# ADC.net
KiCad netlist of a schematic drawn in Altium Designer
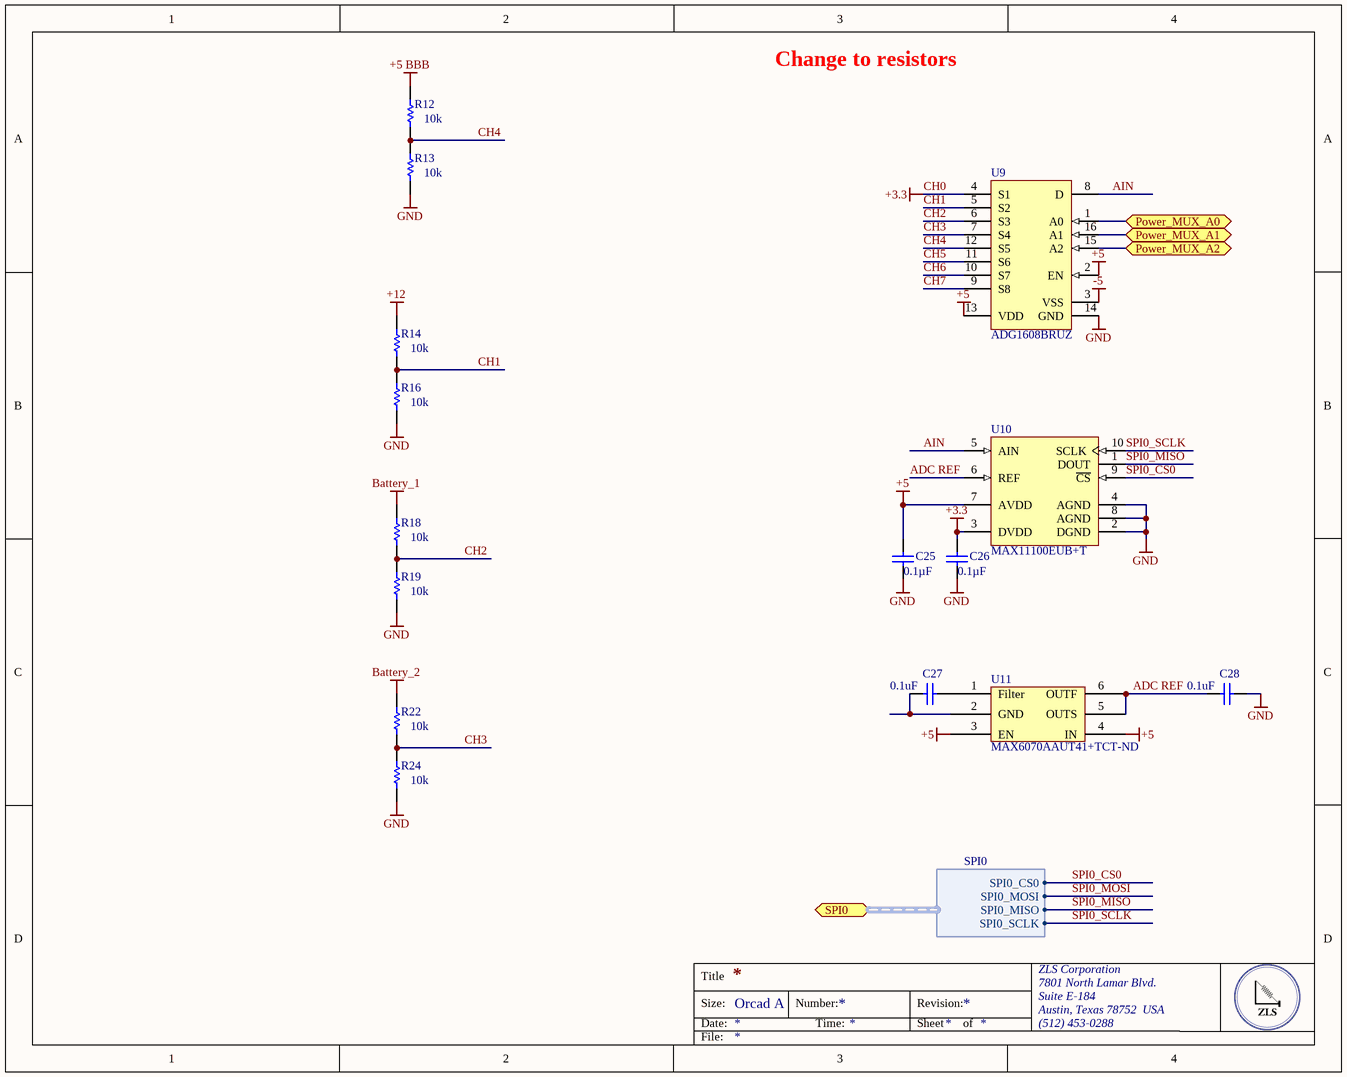
[diagram p0: ADC.SchDoc]

(export (version "E")
  (design (tool "Eeschema 10.0.6"))
  (components
    (comp (ref "C25")
      (value "CAP CER 0.1UF 25V X7R 0805")
      (footprint "CAPC0805(2012)145_N")
      (fields
        (field (name "MANUFACTURER") "Murata Electronics North America")
        (field (name "MANUFACTURER PART NUMBER") "GRM21BR71E104KA01L")
        (field (name "CAPACITANCE") "0.1µF")
        (field (name "TOLERANCE") "±10%")
      )
      (libsource (lib "Altium Content Vault") (part "CMP-1036-04795-1"))
    )
    (comp (ref "C26")
      (value "CAP CER 0.1UF 25V X7R 0805")
      (footprint "CAPC0805(2012)145_N")
      (fields
        (field (name "MANUFACTURER") "Murata Electronics North America")
        (field (name "MANUFACTURER PART NUMBER") "GRM21BR71E104KA01L")
        (field (name "CAPACITANCE") "0.1µF")
        (field (name "TOLERANCE") "±10%")
      )
      (libsource (lib "Altium Content Vault") (part "CMP-1036-04795-1"))
    )
    (comp (ref "C27")
      (value "0.1uF")
      (footprint "CAPC0402(1005)60_L")
      (description "CAP CER 0.1UF 10V X7R 0402")
      (fields
        (field (name "MANUFACTURER") "Murata Electronics North America")
        (field (name "MANUFACTURER PART NUMBER") "GRM155R71A104KA01D")
      )
      (libsource (lib "Altium Content Vault") (part "CMP-1034-00252-1"))
    )
    (comp (ref "C28")
      (value "0.1uF")
      (footprint "CAPC0402(1005)60_L")
      (description "CAP CER 0.1UF 10V X7R 0402")
      (fields
        (field (name "MANUFACTURER") "Murata Electronics North America")
        (field (name "MANUFACTURER PART NUMBER") "GRM155R71A104KA01D")
      )
      (libsource (lib "Altium Content Vault") (part "CMP-1034-00252-1"))
    )
    (comp (ref "R12")
      (value "10k")
      (footprint "RESC0402(1005)_L")
      (libsource (lib "Altium Content Vault") (part "CMP-1011-00927-1"))
    )
    (comp (ref "R13")
      (value "10k")
      (footprint "RESC0402(1005)_L")
      (libsource (lib "Altium Content Vault") (part "CMP-1011-00927-1"))
    )
    (comp (ref "R14")
      (value "10k")
      (footprint "RESC0402(1005)_L")
      (libsource (lib "Altium Content Vault") (part "CMP-1011-00927-1"))
    )
    (comp (ref "R16")
      (value "10k")
      (footprint "RESC0402(1005)_L")
      (libsource (lib "Altium Content Vault") (part "CMP-1011-00927-1"))
    )
    (comp (ref "R18")
      (value "10k")
      (footprint "RESC0402(1005)_L")
      (libsource (lib "Altium Content Vault") (part "CMP-1011-00927-1"))
    )
    (comp (ref "R19")
      (value "10k")
      (footprint "RESC0402(1005)_L")
      (libsource (lib "Altium Content Vault") (part "CMP-1011-00927-1"))
    )
    (comp (ref "R22")
      (value "10k")
      (footprint "RESC0402(1005)_L")
      (libsource (lib "Altium Content Vault") (part "CMP-1011-00927-1"))
    )
    (comp (ref "R24")
      (value "10k")
      (footprint "RESC0402(1005)_L")
      (libsource (lib "Altium Content Vault") (part "CMP-1011-00927-1"))
    )
    (comp (ref "U9")
      (value "ADG1608BRUZ")
      (footprint "ADI-RU-16_M")
      (description "4.5 Ohm Ron, 8-Channel +/-5 V,+12 V, +5 V and +3.3 V Multiplexer, 16-pin SOP (RU-16), Tube")
      (fields (field (name "MANUFACTURER") "Analog Devices"))
      (libsource (lib "Altium Content Vault") (part "ADI-ADG1608-RU-16"))
    )
    (comp (ref "U10")
      (value "MAX11100EUB+T")
      (footprint "U10+2_L")
      (description "16-Bit, +5V, 200ksps ADC with 10uA Shutdown, 10-Pin uMAX, -40°C to +85°C, Pb-Free, Tape and Reel")
      (libsource (lib "Altium Content Vault") (part "CON-ADC-MAX11100-IL10"))
    )
    (comp (ref "U11")
      (value "MAX6070AAUT41+T")
      (footprint "SOT95P280X445-6N")
      (description "IC VREF SERIES 4.096V SOT23")
      (fields
        (field (name "SUPPLIER PART NUMBER 1") "MAX6070AAUT41+TCT-ND")
        (field (name "MANUFACTURER") "Maxim Integrated")
        (field (name "TOLERANCE") "±0.04%")
      )
      (libsource (lib "ZLS_Schematic_lib") (part "MAX6070AAUT41+T"))
    )
  )
  (nets
    (net (code "2") (name "+3.3") (class "Default")
      (node (ref "C26") (pin "1") (pinfunction "1_1") (pintype "passive"))
      (node (ref "U10") (pin "3") (pinfunction "DVDD_3") (pintype "power_in"))
      (node (ref "U9") (pin "4") (pinfunction "S1_4") (pintype "passive"))
    )
    (net (code "3") (name "+5") (class "Default")
      (node (ref "C25") (pin "1") (pinfunction "1_1") (pintype "passive"))
      (node (ref "U10") (pin "7") (pinfunction "AVDD_7") (pintype "power_in"))
      (node (ref "U11") (pin "3") (pinfunction "EN_3") (pintype "passive"))
      (node (ref "U11") (pin "4") (pinfunction "IN_4") (pintype "passive"))
      (node (ref "U9") (pin "13") (pinfunction "VDD_13") (pintype "power_in"))
      (node (ref "U9") (pin "2") (pinfunction "EN_2") (pintype "input"))
    )
    (net (code "4") (name "+5 BBB") (class "Default")
      (node (ref "R12") (pin "2") (pinfunction "2_2") (pintype "passive"))
    )
    (net (code "5") (name "+12") (class "Default")
      (node (ref "R14") (pin "2") (pinfunction "2_2") (pintype "passive"))
    )
    (net (code "6") (name "-5") (class "Default")
      (node (ref "U9") (pin "3") (pinfunction "VSS_3") (pintype "power_in"))
    )
    (net (code "7") (name "/ADC REF") (class "Default")
      (node (ref "C28") (pin "2") (pinfunction "2_2") (pintype "passive"))
      (node (ref "U10") (pin "6") (pinfunction "REF_6") (pintype "input"))
      (node (ref "U11") (pin "5") (pinfunction "OUTS_5") (pintype "passive"))
      (node (ref "U11") (pin "6") (pinfunction "OUTF_6") (pintype "passive"))
    )
    (net (code "8") (name "/AIN") (class "Default")
      (node (ref "U10") (pin "5") (pinfunction "AIN_5") (pintype "input"))
      (node (ref "U9") (pin "8") (pinfunction "D_8") (pintype "passive"))
    )
    (net (code "9") (name "/CH1") (class "Default")
      (node (ref "R14") (pin "1") (pinfunction "1_1") (pintype "passive"))
      (node (ref "R16") (pin "2") (pinfunction "2_2") (pintype "passive"))
      (node (ref "U9") (pin "5") (pinfunction "S2_5") (pintype "passive"))
    )
    (net (code "10") (name "/CH2") (class "Default")
      (node (ref "R18") (pin "1") (pinfunction "1_1") (pintype "passive"))
      (node (ref "R19") (pin "2") (pinfunction "2_2") (pintype "passive"))
      (node (ref "U9") (pin "6") (pinfunction "S3_6") (pintype "passive"))
    )
    (net (code "11") (name "/CH3") (class "Default")
      (node (ref "R22") (pin "1") (pinfunction "1_1") (pintype "passive"))
      (node (ref "R24") (pin "2") (pinfunction "2_2") (pintype "passive"))
      (node (ref "U9") (pin "7") (pinfunction "S4_7") (pintype "passive"))
    )
    (net (code "12") (name "/CH4") (class "Default")
      (node (ref "R12") (pin "1") (pinfunction "1_1") (pintype "passive"))
      (node (ref "R13") (pin "2") (pinfunction "2_2") (pintype "passive"))
      (node (ref "U9") (pin "12") (pinfunction "S5_12") (pintype "passive"))
    )
    (net (code "13") (name "/CH5") (class "Default")
      (node (ref "U9") (pin "11") (pinfunction "S6_11") (pintype "passive"))
    )
    (net (code "14") (name "/CH6") (class "Default")
      (node (ref "U9") (pin "10") (pinfunction "S7_10") (pintype "passive"))
    )
    (net (code "15") (name "/CH7") (class "Default")
      (node (ref "U9") (pin "9") (pinfunction "S8_9") (pintype "passive"))
    )
    (net (code "16") (name "/Power_MUX_A0") (class "Default")
      (node (ref "U9") (pin "1") (pinfunction "A0_1") (pintype "input"))
    )
    (net (code "17") (name "/Power_MUX_A1") (class "Default")
      (node (ref "U9") (pin "16") (pinfunction "A1_16") (pintype "input"))
    )
    (net (code "18") (name "/Power_MUX_A2") (class "Default")
      (node (ref "U9") (pin "15") (pinfunction "A2_15") (pintype "input"))
    )
    (net (code "19") (name "/SPI0_CS0") (class "Default")
      (node (ref "U10") (pin "9") (pinfunction "~{CS}_9") (pintype "input"))
    )
    (net (code "20") (name "/SPI0_MISO") (class "Default")
      (node (ref "U10") (pin "1") (pinfunction "DOUT_1") (pintype "tri_state"))
    )
    (net (code "22") (name "/SPI0_SCLK") (class "Default")
      (node (ref "U10") (pin "10") (pinfunction "SCLK_10") (pintype "input"))
    )
    (net (code "24") (name "Battery_1") (class "Default")
      (node (ref "R18") (pin "2") (pinfunction "2_2") (pintype "passive"))
    )
    (net (code "25") (name "Battery_2") (class "Default")
      (node (ref "R22") (pin "2") (pinfunction "2_2") (pintype "passive"))
    )
    (net (code "26") (name "GND") (class "Default")
      (node (ref "C25") (pin "2") (pinfunction "2_2") (pintype "passive"))
      (node (ref "C26") (pin "2") (pinfunction "2_2") (pintype "passive"))
      (node (ref "C28") (pin "1") (pinfunction "1_1") (pintype "passive"))
      (node (ref "R13") (pin "1") (pinfunction "1_1") (pintype "passive"))
      (node (ref "R16") (pin "1") (pinfunction "1_1") (pintype "passive"))
      (node (ref "R19") (pin "1") (pinfunction "1_1") (pintype "passive"))
      (node (ref "R24") (pin "1") (pinfunction "1_1") (pintype "passive"))
      (node (ref "U10") (pin "2") (pinfunction "DGND_2") (pintype "power_in"))
      (node (ref "U10") (pin "4") (pinfunction "AGND_4") (pintype "power_in"))
      (node (ref "U10") (pin "8") (pinfunction "AGND_8") (pintype "power_in"))
      (node (ref "U9") (pin "14") (pinfunction "GND_14") (pintype "power_in"))
    )
    (net (code "27") (name "Net-(U11-Filter)") (class "Default")
      (node (ref "C27") (pin "1") (pinfunction "1_1") (pintype "passive"))
      (node (ref "U11") (pin "1") (pinfunction "Filter_1") (pintype "passive"))
    )
    (net (code "28") (name "Net-(U11-GND)") (class "Default")
      (node (ref "C27") (pin "2") (pinfunction "2_2") (pintype "passive"))
      (node (ref "U11") (pin "2") (pinfunction "GND_2") (pintype "passive"))
    )
  )
)
